# single-gates-THT.net
KiCad netlist of a schematic drawn in EAGLE
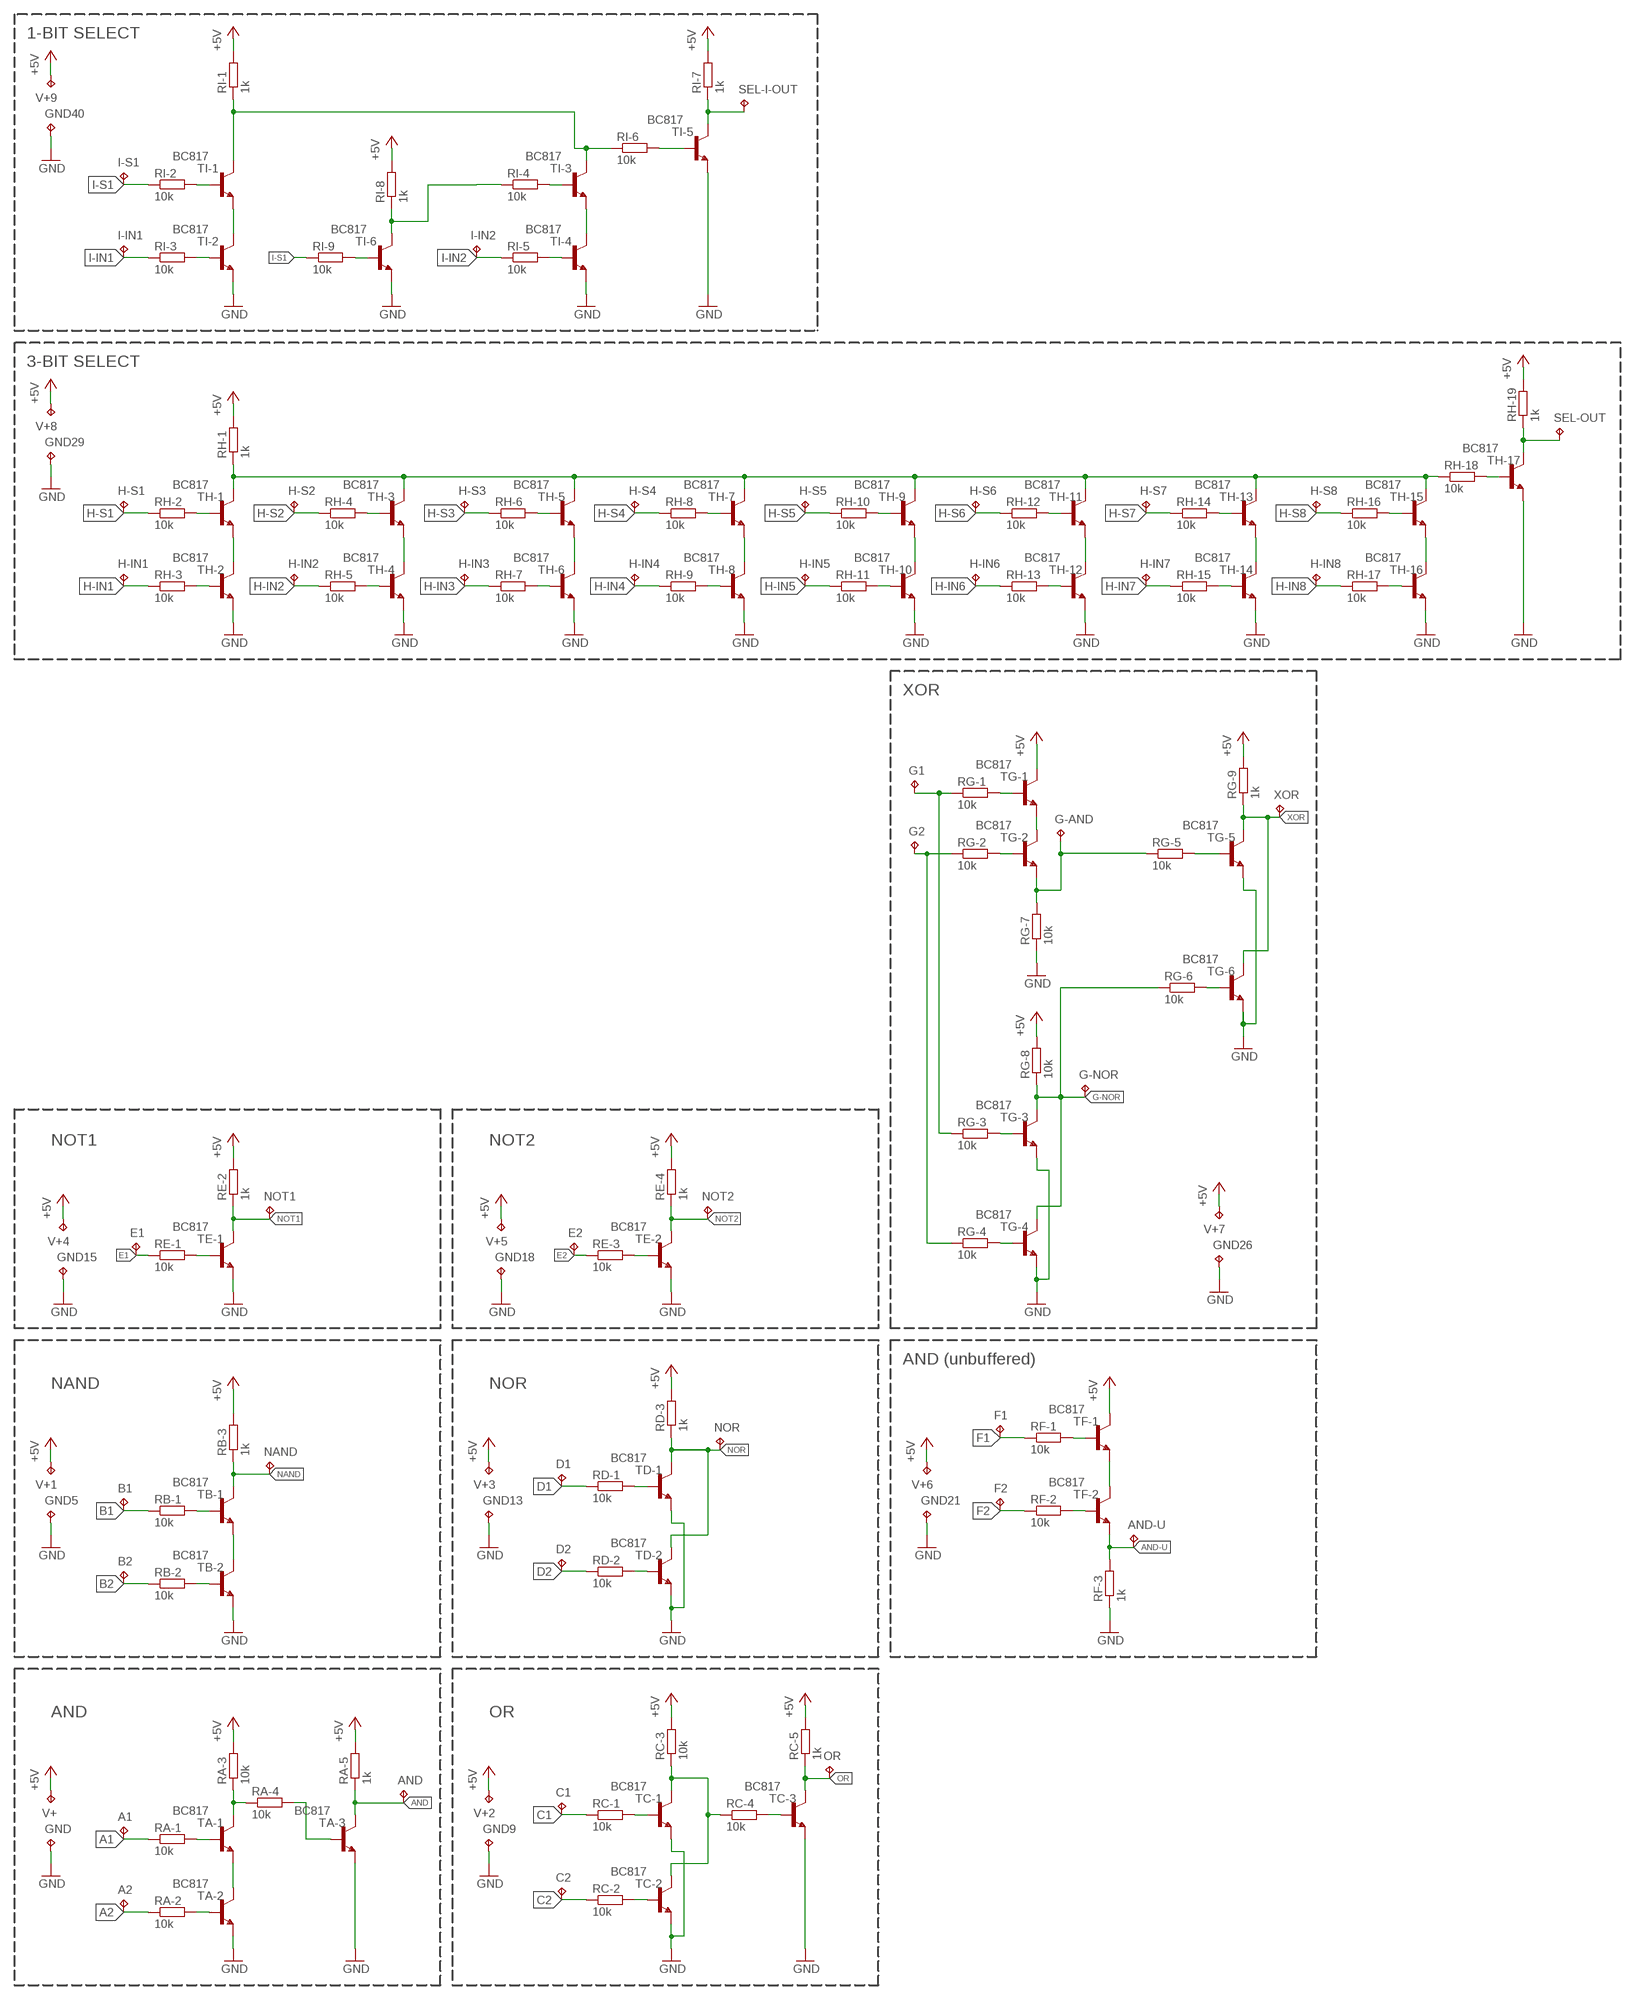
[diagram p0: schematic, sheet 1]

(export (version "E")
  (design (tool "Eeschema 10.0.6"))
  (components
    (comp (ref "A1")
      (value "TPTP07R")
      (footprint "eagle-import:TP07R")
      (libsource (lib "eagle-import") (part "TPTP07R"))
    )
    (comp (ref "A2")
      (value "TPTP07R")
      (footprint "eagle-import:TP07R")
      (libsource (lib "eagle-import") (part "TPTP07R"))
    )
    (comp (ref "AND")
      (value "TPTP07R")
      (footprint "eagle-import:TP07R")
      (libsource (lib "eagle-import") (part "TPTP07R"))
    )
    (comp (ref "AND-U")
      (value "TPTP07R")
      (footprint "eagle-import:TP07R")
      (libsource (lib "eagle-import") (part "TPTP07R"))
    )
    (comp (ref "B1")
      (value "TPTP07R")
      (footprint "eagle-import:TP07R")
      (libsource (lib "eagle-import") (part "TPTP07R"))
    )
    (comp (ref "B2")
      (value "TPTP07R")
      (footprint "eagle-import:TP07R")
      (libsource (lib "eagle-import") (part "TPTP07R"))
    )
    (comp (ref "C1")
      (value "TPTP07R")
      (footprint "eagle-import:TP07R")
      (libsource (lib "eagle-import") (part "TPTP07R"))
    )
    (comp (ref "C2")
      (value "TPTP07R")
      (footprint "eagle-import:TP07R")
      (libsource (lib "eagle-import") (part "TPTP07R"))
    )
    (comp (ref "D1")
      (value "TPTP07R")
      (footprint "eagle-import:TP07R")
      (libsource (lib "eagle-import") (part "TPTP07R"))
    )
    (comp (ref "D2")
      (value "TPTP07R")
      (footprint "eagle-import:TP07R")
      (libsource (lib "eagle-import") (part "TPTP07R"))
    )
    (comp (ref "E1")
      (value "TPTP07R")
      (footprint "eagle-import:TP07R")
      (libsource (lib "eagle-import") (part "TPTP07R"))
    )
    (comp (ref "E2")
      (value "TPTP07R")
      (footprint "eagle-import:TP07R")
      (libsource (lib "eagle-import") (part "TPTP07R"))
    )
    (comp (ref "F1")
      (value "TPTP07R")
      (footprint "eagle-import:TP07R")
      (libsource (lib "eagle-import") (part "TPTP07R"))
    )
    (comp (ref "F2")
      (value "TPTP07R")
      (footprint "eagle-import:TP07R")
      (libsource (lib "eagle-import") (part "TPTP07R"))
    )
    (comp (ref "G-AND")
      (value "TPTP07R")
      (footprint "eagle-import:TP07R")
      (libsource (lib "eagle-import") (part "TPTP07R"))
    )
    (comp (ref "G-NOR")
      (value "TPTP07R")
      (footprint "eagle-import:TP07R")
      (libsource (lib "eagle-import") (part "TPTP07R"))
    )
    (comp (ref "G1")
      (value "TPTP07R")
      (footprint "eagle-import:TP07R")
      (libsource (lib "eagle-import") (part "TPTP07R"))
    )
    (comp (ref "G2")
      (value "TPTP07R")
      (footprint "eagle-import:TP07R")
      (libsource (lib "eagle-import") (part "TPTP07R"))
    )
    (comp (ref "GND")
      (value "TPTP07R")
      (footprint "eagle-import:TP07R")
      (libsource (lib "eagle-import") (part "TPTP07R"))
    )
    (comp (ref "GND5")
      (value "TPTP07R")
      (footprint "eagle-import:TP07R")
      (libsource (lib "eagle-import") (part "TPTP07R"))
    )
    (comp (ref "GND9")
      (value "TPTP07R")
      (footprint "eagle-import:TP07R")
      (libsource (lib "eagle-import") (part "TPTP07R"))
    )
    (comp (ref "GND13")
      (value "TPTP07R")
      (footprint "eagle-import:TP07R")
      (libsource (lib "eagle-import") (part "TPTP07R"))
    )
    (comp (ref "GND15")
      (value "TPTP07R")
      (footprint "eagle-import:TP07R")
      (libsource (lib "eagle-import") (part "TPTP07R"))
    )
    (comp (ref "GND18")
      (value "TPTP07R")
      (footprint "eagle-import:TP07R")
      (libsource (lib "eagle-import") (part "TPTP07R"))
    )
    (comp (ref "GND21")
      (value "TPTP07R")
      (footprint "eagle-import:TP07R")
      (libsource (lib "eagle-import") (part "TPTP07R"))
    )
    (comp (ref "GND26")
      (value "TPTP07R")
      (footprint "eagle-import:TP07R")
      (libsource (lib "eagle-import") (part "TPTP07R"))
    )
    (comp (ref "GND29")
      (value "TPTP07R")
      (footprint "eagle-import:TP07R")
      (libsource (lib "eagle-import") (part "TPTP07R"))
    )
    (comp (ref "GND40")
      (value "TPTP07R")
      (footprint "eagle-import:TP07R")
      (libsource (lib "eagle-import") (part "TPTP07R"))
    )
    (comp (ref "H-IN1")
      (value "TPTP07R")
      (footprint "eagle-import:TP07R")
      (libsource (lib "eagle-import") (part "TPTP07R"))
    )
    (comp (ref "H-IN2")
      (value "TPTP07R")
      (footprint "eagle-import:TP07R")
      (libsource (lib "eagle-import") (part "TPTP07R"))
    )
    (comp (ref "H-IN3")
      (value "TPTP07R")
      (footprint "eagle-import:TP07R")
      (libsource (lib "eagle-import") (part "TPTP07R"))
    )
    (comp (ref "H-IN4")
      (value "TPTP07R")
      (footprint "eagle-import:TP07R")
      (libsource (lib "eagle-import") (part "TPTP07R"))
    )
    (comp (ref "H-IN5")
      (value "TPTP07R")
      (footprint "eagle-import:TP07R")
      (libsource (lib "eagle-import") (part "TPTP07R"))
    )
    (comp (ref "H-IN6")
      (value "TPTP07R")
      (footprint "eagle-import:TP07R")
      (libsource (lib "eagle-import") (part "TPTP07R"))
    )
    (comp (ref "H-IN7")
      (value "TPTP07R")
      (footprint "eagle-import:TP07R")
      (libsource (lib "eagle-import") (part "TPTP07R"))
    )
    (comp (ref "H-IN8")
      (value "TPTP07R")
      (footprint "eagle-import:TP07R")
      (libsource (lib "eagle-import") (part "TPTP07R"))
    )
    (comp (ref "H-S1")
      (value "TPTP07R")
      (footprint "eagle-import:TP07R")
      (libsource (lib "eagle-import") (part "TPTP07R"))
    )
    (comp (ref "H-S2")
      (value "TPTP07R")
      (footprint "eagle-import:TP07R")
      (libsource (lib "eagle-import") (part "TPTP07R"))
    )
    (comp (ref "H-S3")
      (value "TPTP07R")
      (footprint "eagle-import:TP07R")
      (libsource (lib "eagle-import") (part "TPTP07R"))
    )
    (comp (ref "H-S4")
      (value "TPTP07R")
      (footprint "eagle-import:TP07R")
      (libsource (lib "eagle-import") (part "TPTP07R"))
    )
    (comp (ref "H-S5")
      (value "TPTP07R")
      (footprint "eagle-import:TP07R")
      (libsource (lib "eagle-import") (part "TPTP07R"))
    )
    (comp (ref "H-S6")
      (value "TPTP07R")
      (footprint "eagle-import:TP07R")
      (libsource (lib "eagle-import") (part "TPTP07R"))
    )
    (comp (ref "H-S7")
      (value "TPTP07R")
      (footprint "eagle-import:TP07R")
      (libsource (lib "eagle-import") (part "TPTP07R"))
    )
    (comp (ref "H-S8")
      (value "TPTP07R")
      (footprint "eagle-import:TP07R")
      (libsource (lib "eagle-import") (part "TPTP07R"))
    )
    (comp (ref "I-IN1")
      (value "TPTP07R")
      (footprint "eagle-import:TP07R")
      (libsource (lib "eagle-import") (part "TPTP07R"))
    )
    (comp (ref "I-IN2")
      (value "TPTP07R")
      (footprint "eagle-import:TP07R")
      (libsource (lib "eagle-import") (part "TPTP07R"))
    )
    (comp (ref "I-S1")
      (value "TPTP07R")
      (footprint "eagle-import:TP07R")
      (libsource (lib "eagle-import") (part "TPTP07R"))
    )
    (comp (ref "NAND")
      (value "TPTP07R")
      (footprint "eagle-import:TP07R")
      (libsource (lib "eagle-import") (part "TPTP07R"))
    )
    (comp (ref "NOR")
      (value "TPTP07R")
      (footprint "eagle-import:TP07R")
      (libsource (lib "eagle-import") (part "TPTP07R"))
    )
    (comp (ref "NOT1")
      (value "TPTP07R")
      (footprint "eagle-import:TP07R")
      (libsource (lib "eagle-import") (part "TPTP07R"))
    )
    (comp (ref "NOT2")
      (value "TPTP07R")
      (footprint "eagle-import:TP07R")
      (libsource (lib "eagle-import") (part "TPTP07R"))
    )
    (comp (ref "OR")
      (value "TPTP07R")
      (footprint "eagle-import:TP07R")
      (libsource (lib "eagle-import") (part "TPTP07R"))
    )
    (comp (ref "RA-1")
      (value "10k")
      (footprint "eagle-import:0207_7")
      (libsource (lib "eagle-import") (part "R-EU_0207/7"))
    )
    (comp (ref "RA-2")
      (value "10k")
      (footprint "eagle-import:0207_7")
      (libsource (lib "eagle-import") (part "R-EU_0207/7"))
    )
    (comp (ref "RA-3")
      (value "10k")
      (footprint "eagle-import:0207_7")
      (libsource (lib "eagle-import") (part "R-EU_0207/7"))
    )
    (comp (ref "RA-4")
      (value "10k")
      (footprint "eagle-import:0207_7")
      (libsource (lib "eagle-import") (part "R-EU_0207/7"))
    )
    (comp (ref "RA-5")
      (value "1k")
      (footprint "eagle-import:0207_7")
      (libsource (lib "eagle-import") (part "R-EU_0207/7"))
    )
    (comp (ref "RB-1")
      (value "10k")
      (footprint "eagle-import:0207_7")
      (libsource (lib "eagle-import") (part "R-EU_0207/7"))
    )
    (comp (ref "RB-2")
      (value "10k")
      (footprint "eagle-import:0207_7")
      (libsource (lib "eagle-import") (part "R-EU_0207/7"))
    )
    (comp (ref "RB-3")
      (value "1k")
      (footprint "eagle-import:0207_7")
      (libsource (lib "eagle-import") (part "R-EU_0207/7"))
    )
    (comp (ref "RC-1")
      (value "10k")
      (footprint "eagle-import:0207_7")
      (libsource (lib "eagle-import") (part "R-EU_0207/7"))
    )
    (comp (ref "RC-2")
      (value "10k")
      (footprint "eagle-import:0207_7")
      (libsource (lib "eagle-import") (part "R-EU_0207/7"))
    )
    (comp (ref "RC-3")
      (value "10k")
      (footprint "eagle-import:0207_7")
      (libsource (lib "eagle-import") (part "R-EU_0207/7"))
    )
    (comp (ref "RC-4")
      (value "10k")
      (footprint "eagle-import:0207_7")
      (libsource (lib "eagle-import") (part "R-EU_0207/7"))
    )
    (comp (ref "RC-5")
      (value "1k")
      (footprint "eagle-import:0207_7")
      (libsource (lib "eagle-import") (part "R-EU_0207/7"))
    )
    (comp (ref "RD-1")
      (value "10k")
      (footprint "eagle-import:0207_7")
      (libsource (lib "eagle-import") (part "R-EU_0207/7"))
    )
    (comp (ref "RD-2")
      (value "10k")
      (footprint "eagle-import:0207_7")
      (libsource (lib "eagle-import") (part "R-EU_0207/7"))
    )
    (comp (ref "RD-3")
      (value "1k")
      (footprint "eagle-import:0207_7")
      (libsource (lib "eagle-import") (part "R-EU_0207/7"))
    )
    (comp (ref "RE-1")
      (value "10k")
      (footprint "eagle-import:0207_7")
      (libsource (lib "eagle-import") (part "R-EU_0207/7"))
    )
    (comp (ref "RE-2")
      (value "1k")
      (footprint "eagle-import:0207_7")
      (libsource (lib "eagle-import") (part "R-EU_0207/7"))
    )
    (comp (ref "RE-3")
      (value "10k")
      (footprint "eagle-import:0207_7")
      (libsource (lib "eagle-import") (part "R-EU_0207/7"))
    )
    (comp (ref "RE-4")
      (value "1k")
      (footprint "eagle-import:0207_7")
      (libsource (lib "eagle-import") (part "R-EU_0207/7"))
    )
    (comp (ref "RF-1")
      (value "10k")
      (footprint "eagle-import:0207_7")
      (libsource (lib "eagle-import") (part "R-EU_0207/7"))
    )
    (comp (ref "RF-2")
      (value "10k")
      (footprint "eagle-import:0207_7")
      (libsource (lib "eagle-import") (part "R-EU_0207/7"))
    )
    (comp (ref "RF-3")
      (value "1k")
      (footprint "eagle-import:0207_7")
      (libsource (lib "eagle-import") (part "R-EU_0207/7"))
    )
    (comp (ref "RG-1")
      (value "10k")
      (footprint "eagle-import:0207_7")
      (libsource (lib "eagle-import") (part "R-EU_0207/7"))
    )
    (comp (ref "RG-2")
      (value "10k")
      (footprint "eagle-import:0207_7")
      (libsource (lib "eagle-import") (part "R-EU_0207/7"))
    )
    (comp (ref "RG-3")
      (value "10k")
      (footprint "eagle-import:0207_7")
      (libsource (lib "eagle-import") (part "R-EU_0207/7"))
    )
    (comp (ref "RG-4")
      (value "10k")
      (footprint "eagle-import:0207_7")
      (libsource (lib "eagle-import") (part "R-EU_0207/7"))
    )
    (comp (ref "RG-5")
      (value "10k")
      (footprint "eagle-import:0207_7")
      (libsource (lib "eagle-import") (part "R-EU_0207/7"))
    )
    (comp (ref "RG-6")
      (value "10k")
      (footprint "eagle-import:0207_7")
      (libsource (lib "eagle-import") (part "R-EU_0207/7"))
    )
    (comp (ref "RG-7")
      (value "10k")
      (footprint "eagle-import:0207_7")
      (libsource (lib "eagle-import") (part "R-EU_0207/7"))
    )
    (comp (ref "RG-8")
      (value "10k")
      (footprint "eagle-import:0207_7")
      (libsource (lib "eagle-import") (part "R-EU_0207/7"))
    )
    (comp (ref "RG-9")
      (value "1k")
      (footprint "eagle-import:0207_7")
      (libsource (lib "eagle-import") (part "R-EU_0207/7"))
    )
    (comp (ref "RH-1")
      (value "1k")
      (footprint "eagle-import:0207_7")
      (libsource (lib "eagle-import") (part "R-EU_0207/7"))
    )
    (comp (ref "RH-2")
      (value "10k")
      (footprint "eagle-import:0207_7")
      (libsource (lib "eagle-import") (part "R-EU_0207/7"))
    )
    (comp (ref "RH-3")
      (value "10k")
      (footprint "eagle-import:0207_7")
      (libsource (lib "eagle-import") (part "R-EU_0207/7"))
    )
    (comp (ref "RH-4")
      (value "10k")
      (footprint "eagle-import:0207_7")
      (libsource (lib "eagle-import") (part "R-EU_0207/7"))
    )
    (comp (ref "RH-5")
      (value "10k")
      (footprint "eagle-import:0207_7")
      (libsource (lib "eagle-import") (part "R-EU_0207/7"))
    )
    (comp (ref "RH-6")
      (value "10k")
      (footprint "eagle-import:0207_7")
      (libsource (lib "eagle-import") (part "R-EU_0207/7"))
    )
    (comp (ref "RH-7")
      (value "10k")
      (footprint "eagle-import:0207_7")
      (libsource (lib "eagle-import") (part "R-EU_0207/7"))
    )
    (comp (ref "RH-8")
      (value "10k")
      (footprint "eagle-import:0207_7")
      (libsource (lib "eagle-import") (part "R-EU_0207/7"))
    )
    (comp (ref "RH-9")
      (value "10k")
      (footprint "eagle-import:0207_7")
      (libsource (lib "eagle-import") (part "R-EU_0207/7"))
    )
    (comp (ref "RH-10")
      (value "10k")
      (footprint "eagle-import:0207_7")
      (libsource (lib "eagle-import") (part "R-EU_0207/7"))
    )
    (comp (ref "RH-11")
      (value "10k")
      (footprint "eagle-import:0207_7")
      (libsource (lib "eagle-import") (part "R-EU_0207/7"))
    )
    (comp (ref "RH-12")
      (value "10k")
      (footprint "eagle-import:0207_7")
      (libsource (lib "eagle-import") (part "R-EU_0207/7"))
    )
    (comp (ref "RH-13")
      (value "10k")
      (footprint "eagle-import:0207_7")
      (libsource (lib "eagle-import") (part "R-EU_0207/7"))
    )
    (comp (ref "RH-14")
      (value "10k")
      (footprint "eagle-import:0207_7")
      (libsource (lib "eagle-import") (part "R-EU_0207/7"))
    )
    (comp (ref "RH-15")
      (value "10k")
      (footprint "eagle-import:0207_7")
      (libsource (lib "eagle-import") (part "R-EU_0207/7"))
    )
    (comp (ref "RH-16")
      (value "10k")
      (footprint "eagle-import:0207_7")
      (libsource (lib "eagle-import") (part "R-EU_0207/7"))
    )
    (comp (ref "RH-17")
      (value "10k")
      (footprint "eagle-import:0207_7")
      (libsource (lib "eagle-import") (part "R-EU_0207/7"))
    )
    (comp (ref "RH-18")
      (value "10k")
      (footprint "eagle-import:0207_7")
      (libsource (lib "eagle-import") (part "R-EU_0207/7"))
    )
    (comp (ref "RH-19")
      (value "1k")
      (footprint "eagle-import:0207_7")
      (libsource (lib "eagle-import") (part "R-EU_0207/7"))
    )
    (comp (ref "RI-1")
      (value "1k")
      (footprint "eagle-import:0207_7")
      (libsource (lib "eagle-import") (part "R-EU_0207/7"))
    )
    (comp (ref "RI-2")
      (value "10k")
      (footprint "eagle-import:0207_7")
      (libsource (lib "eagle-import") (part "R-EU_0207/7"))
    )
    (comp (ref "RI-3")
      (value "10k")
      (footprint "eagle-import:0207_7")
      (libsource (lib "eagle-import") (part "R-EU_0207/7"))
    )
    (comp (ref "RI-4")
      (value "10k")
      (footprint "eagle-import:0207_7")
      (libsource (lib "eagle-import") (part "R-EU_0207/7"))
    )
    (comp (ref "RI-5")
      (value "10k")
      (footprint "eagle-import:0207_7")
      (libsource (lib "eagle-import") (part "R-EU_0207/7"))
    )
    (comp (ref "RI-6")
      (value "10k")
      (footprint "eagle-import:0207_7")
      (libsource (lib "eagle-import") (part "R-EU_0207/7"))
    )
    (comp (ref "RI-7")
      (value "1k")
      (footprint "eagle-import:0207_7")
      (libsource (lib "eagle-import") (part "R-EU_0207/7"))
    )
    (comp (ref "RI-8")
      (value "1k")
      (footprint "eagle-import:0207_7")
      (libsource (lib "eagle-import") (part "R-EU_0207/7"))
    )
    (comp (ref "RI-9")
      (value "10k")
      (footprint "eagle-import:0207_7")
      (libsource (lib "eagle-import") (part "R-EU_0207/7"))
    )
    (comp (ref "SEL-I-OUT")
      (value "TPTP07R")
      (footprint "eagle-import:TP07R")
      (libsource (lib "eagle-import") (part "TPTP07R"))
    )
    (comp (ref "SEL-OUT")
      (value "TPTP07R")
      (footprint "eagle-import:TP07R")
      (libsource (lib "eagle-import") (part "TPTP07R"))
    )
    (comp (ref "TA-1")
      (value "BC817")
      (footprint "eagle-import:TO92")
      (libsource (lib "eagle-import") (part "BC547A"))
    )
    (comp (ref "TA-2")
      (value "BC817")
      (footprint "eagle-import:TO92")
      (libsource (lib "eagle-import") (part "BC547A"))
    )
    (comp (ref "TA-3")
      (value "BC817")
      (footprint "eagle-import:TO92")
      (libsource (lib "eagle-import") (part "BC547A"))
    )
    (comp (ref "TB-1")
      (value "BC817")
      (footprint "eagle-import:TO92")
      (libsource (lib "eagle-import") (part "BC547A"))
    )
    (comp (ref "TB-2")
      (value "BC817")
      (footprint "eagle-import:TO92")
      (libsource (lib "eagle-import") (part "BC547A"))
    )
    (comp (ref "TC-1")
      (value "BC817")
      (footprint "eagle-import:TO92")
      (libsource (lib "eagle-import") (part "BC547A"))
    )
    (comp (ref "TC-2")
      (value "BC817")
      (footprint "eagle-import:TO92")
      (libsource (lib "eagle-import") (part "BC547A"))
    )
    (comp (ref "TC-3")
      (value "BC817")
      (footprint "eagle-import:TO92")
      (libsource (lib "eagle-import") (part "BC547A"))
    )
    (comp (ref "TD-1")
      (value "BC817")
      (footprint "eagle-import:TO92")
      (libsource (lib "eagle-import") (part "BC547A"))
    )
    (comp (ref "TD-2")
      (value "BC817")
      (footprint "eagle-import:TO92")
      (libsource (lib "eagle-import") (part "BC547A"))
    )
    (comp (ref "TE-1")
      (value "BC817")
      (footprint "eagle-import:TO92")
      (libsource (lib "eagle-import") (part "BC547A"))
    )
    (comp (ref "TE-2")
      (value "BC817")
      (footprint "eagle-import:TO92")
      (libsource (lib "eagle-import") (part "BC547A"))
    )
    (comp (ref "TF-1")
      (value "BC817")
      (footprint "eagle-import:TO92")
      (libsource (lib "eagle-import") (part "BC547A"))
    )
    (comp (ref "TF-2")
      (value "BC817")
      (footprint "eagle-import:TO92")
      (libsource (lib "eagle-import") (part "BC547A"))
    )
    (comp (ref "TG-1")
      (value "BC817")
      (footprint "eagle-import:TO92")
      (libsource (lib "eagle-import") (part "BC547A"))
    )
    (comp (ref "TG-2")
      (value "BC817")
      (footprint "eagle-import:TO92")
      (libsource (lib "eagle-import") (part "BC547A"))
    )
    (comp (ref "TG-3")
      (value "BC817")
      (footprint "eagle-import:TO92")
      (libsource (lib "eagle-import") (part "BC547A"))
    )
    (comp (ref "TG-4")
      (value "BC817")
      (footprint "eagle-import:TO92")
      (libsource (lib "eagle-import") (part "BC547A"))
    )
    (comp (ref "TG-5")
      (value "BC817")
      (footprint "eagle-import:TO92")
      (libsource (lib "eagle-import") (part "BC547A"))
    )
    (comp (ref "TG-6")
      (value "BC817")
      (footprint "eagle-import:TO92")
      (libsource (lib "eagle-import") (part "BC547A"))
    )
    (comp (ref "TH-1")
      (value "BC817")
      (footprint "eagle-import:TO92")
      (libsource (lib "eagle-import") (part "BC547A"))
    )
    (comp (ref "TH-2")
      (value "BC817")
      (footprint "eagle-import:TO92")
      (libsource (lib "eagle-import") (part "BC547A"))
    )
    (comp (ref "TH-3")
      (value "BC817")
      (footprint "eagle-import:TO92")
      (libsource (lib "eagle-import") (part "BC547A"))
    )
    (comp (ref "TH-4")
      (value "BC817")
      (footprint "eagle-import:TO92")
      (libsource (lib "eagle-import") (part "BC547A"))
    )
    (comp (ref "TH-5")
      (value "BC817")
      (footprint "eagle-import:TO92")
      (libsource (lib "eagle-import") (part "BC547A"))
    )
    (comp (ref "TH-6")
      (value "BC817")
      (footprint "eagle-import:TO92")
      (libsource (lib "eagle-import") (part "BC547A"))
    )
    (comp (ref "TH-7")
      (value "BC817")
      (footprint "eagle-import:TO92")
      (libsource (lib "eagle-import") (part "BC547A"))
    )
    (comp (ref "TH-8")
      (value "BC817")
      (footprint "eagle-import:TO92")
      (libsource (lib "eagle-import") (part "BC547A"))
    )
    (comp (ref "TH-9")
      (value "BC817")
      (footprint "eagle-import:TO92")
      (libsource (lib "eagle-import") (part "BC547A"))
    )
    (comp (ref "TH-10")
      (value "BC817")
      (footprint "eagle-import:TO92")
      (libsource (lib "eagle-import") (part "BC547A"))
    )
    (comp (ref "TH-11")
      (value "BC817")
      (footprint "eagle-import:TO92")
      (libsource (lib "eagle-import") (part "BC547A"))
    )
    (comp (ref "TH-12")
      (value "BC817")
      (footprint "eagle-import:TO92")
      (libsource (lib "eagle-import") (part "BC547A"))
    )
    (comp (ref "TH-13")
      (value "BC817")
      (footprint "eagle-import:TO92")
      (libsource (lib "eagle-import") (part "BC547A"))
    )
    (comp (ref "TH-14")
      (value "BC817")
      (footprint "eagle-import:TO92")
      (libsource (lib "eagle-import") (part "BC547A"))
    )
    (comp (ref "TH-15")
      (value "BC817")
      (footprint "eagle-import:TO92")
      (libsource (lib "eagle-import") (part "BC547A"))
    )
    (comp (ref "TH-16")
      (value "BC817")
      (footprint "eagle-import:TO92")
      (libsource (lib "eagle-import") (part "BC547A"))
    )
    (comp (ref "TH-17")
      (value "BC817")
      (footprint "eagle-import:TO92")
      (libsource (lib "eagle-import") (part "BC547A"))
    )
    (comp (ref "TI-1")
      (value "BC817")
      (footprint "eagle-import:TO92")
      (libsource (lib "eagle-import") (part "BC547A"))
    )
    (comp (ref "TI-2")
      (value "BC817")
      (footprint "eagle-import:TO92")
      (libsource (lib "eagle-import") (part "BC547A"))
    )
    (comp (ref "TI-3")
      (value "BC817")
      (footprint "eagle-import:TO92")
      (libsource (lib "eagle-import") (part "BC547A"))
    )
    (comp (ref "TI-4")
      (value "BC817")
      (footprint "eagle-import:TO92")
      (libsource (lib "eagle-import") (part "BC547A"))
    )
    (comp (ref "TI-5")
      (value "BC817")
      (footprint "eagle-import:TO92")
      (libsource (lib "eagle-import") (part "BC547A"))
    )
    (comp (ref "TI-6")
      (value "BC817")
      (footprint "eagle-import:TO92")
      (libsource (lib "eagle-import") (part "BC547A"))
    )
    (comp (ref "V+")
      (value "TPTP07R")
      (footprint "eagle-import:TP07R")
      (libsource (lib "eagle-import") (part "TPTP07R"))
    )
    (comp (ref "V+1")
      (value "TPTP07R")
      (footprint "eagle-import:TP07R")
      (libsource (lib "eagle-import") (part "TPTP07R"))
    )
    (comp (ref "V+2")
      (value "TPTP07R")
      (footprint "eagle-import:TP07R")
      (libsource (lib "eagle-import") (part "TPTP07R"))
    )
    (comp (ref "V+3")
      (value "TPTP07R")
      (footprint "eagle-import:TP07R")
      (libsource (lib "eagle-import") (part "TPTP07R"))
    )
    (comp (ref "V+4")
      (value "TPTP07R")
      (footprint "eagle-import:TP07R")
      (libsource (lib "eagle-import") (part "TPTP07R"))
    )
    (comp (ref "V+5")
      (value "TPTP07R")
      (footprint "eagle-import:TP07R")
      (libsource (lib "eagle-import") (part "TPTP07R"))
    )
    (comp (ref "V+6")
      (value "TPTP07R")
      (footprint "eagle-import:TP07R")
      (libsource (lib "eagle-import") (part "TPTP07R"))
    )
    (comp (ref "V+7")
      (value "TPTP07R")
      (footprint "eagle-import:TP07R")
      (libsource (lib "eagle-import") (part "TPTP07R"))
    )
    (comp (ref "V+8")
      (value "TPTP07R")
      (footprint "eagle-import:TP07R")
      (libsource (lib "eagle-import") (part "TPTP07R"))
    )
    (comp (ref "V+9")
      (value "TPTP07R")
      (footprint "eagle-import:TP07R")
      (libsource (lib "eagle-import") (part "TPTP07R"))
    )
    (comp (ref "XOR")
      (value "TPTP07R")
      (footprint "eagle-import:TP07R")
      (libsource (lib "eagle-import") (part "TPTP07R"))
    )
  )
  (nets
    (net (code "1") (name "+5V") (class "Default")
      (node (ref "RA-3") (pin "2") (pinfunction "2_2") (pintype "passive"))
      (node (ref "RA-5") (pin "2") (pinfunction "2_2") (pintype "passive"))
      (node (ref "RB-3") (pin "2") (pinfunction "2_2") (pintype "passive"))
      (node (ref "RC-3") (pin "2") (pinfunction "2_2") (pintype "passive"))
      (node (ref "RC-5") (pin "2") (pinfunction "2_2") (pintype "passive"))
      (node (ref "RD-3") (pin "2") (pinfunction "2_2") (pintype "passive"))
      (node (ref "RE-2") (pin "2") (pinfunction "2_2") (pintype "passive"))
      (node (ref "RE-4") (pin "2") (pinfunction "2_2") (pintype "passive"))
      (node (ref "RG-8") (pin "2") (pinfunction "2_2") (pintype "passive"))
      (node (ref "RG-9") (pin "2") (pinfunction "2_2") (pintype "passive"))
      (node (ref "RH-1") (pin "2") (pinfunction "2_2") (pintype "passive"))
      (node (ref "RH-19") (pin "2") (pinfunction "2_2") (pintype "passive"))
      (node (ref "RI-1") (pin "2") (pinfunction "2_2") (pintype "passive"))
      (node (ref "RI-7") (pin "2") (pinfunction "2_2") (pintype "passive"))
      (node (ref "RI-8") (pin "2") (pinfunction "2_2") (pintype "passive"))
      (node (ref "TF-1") (pin "3") (pinfunction "C_3") (pintype "passive"))
      (node (ref "TG-1") (pin "3") (pinfunction "C_3") (pintype "passive"))
      (node (ref "V+") (pin "TP") (pinfunction "TP_TP") (pintype "input"))
      (node (ref "V+1") (pin "TP") (pinfunction "TP_TP") (pintype "input"))
      (node (ref "V+2") (pin "TP") (pinfunction "TP_TP") (pintype "input"))
      (node (ref "V+3") (pin "TP") (pinfunction "TP_TP") (pintype "input"))
      (node (ref "V+4") (pin "TP") (pinfunction "TP_TP") (pintype "input"))
      (node (ref "V+5") (pin "TP") (pinfunction "TP_TP") (pintype "input"))
      (node (ref "V+6") (pin "TP") (pinfunction "TP_TP") (pintype "input"))
      (node (ref "V+7") (pin "TP") (pinfunction "TP_TP") (pintype "input"))
      (node (ref "V+8") (pin "TP") (pinfunction "TP_TP") (pintype "input"))
      (node (ref "V+9") (pin "TP") (pinfunction "TP_TP") (pintype "input"))
    )
    (net (code "2") (name "A1") (class "Default")
      (node (ref "A1") (pin "TP") (pinfunction "TP_TP") (pintype "input"))
      (node (ref "RA-1") (pin "1") (pinfunction "1_1") (pintype "passive"))
    )
    (net (code "3") (name "A2") (class "Default")
      (node (ref "A2") (pin "TP") (pinfunction "TP_TP") (pintype "input"))
      (node (ref "RA-2") (pin "1") (pinfunction "1_1") (pintype "passive"))
    )
    (net (code "4") (name "AND") (class "Default")
      (node (ref "AND") (pin "TP") (pinfunction "TP_TP") (pintype "input"))
      (node (ref "RA-5") (pin "1") (pinfunction "1_1") (pintype "passive"))
      (node (ref "TA-3") (pin "3") (pinfunction "C_3") (pintype "passive"))
    )
    (net (code "5") (name "AND-U") (class "Default")
      (node (ref "AND-U") (pin "TP") (pinfunction "TP_TP") (pintype "input"))
      (node (ref "RF-3") (pin "2") (pinfunction "2_2") (pintype "passive"))
      (node (ref "TF-2") (pin "1") (pinfunction "E_1") (pintype "passive"))
    )
    (net (code "6") (name "B1") (class "Default")
      (node (ref "B1") (pin "TP") (pinfunction "TP_TP") (pintype "input"))
      (node (ref "RB-1") (pin "1") (pinfunction "1_1") (pintype "passive"))
    )
    (net (code "7") (name "B2") (class "Default")
      (node (ref "B2") (pin "TP") (pinfunction "TP_TP") (pintype "input"))
      (node (ref "RB-2") (pin "1") (pinfunction "1_1") (pintype "passive"))
    )
    (net (code "8") (name "C1") (class "Default")
      (node (ref "C1") (pin "TP") (pinfunction "TP_TP") (pintype "input"))
      (node (ref "RC-1") (pin "1") (pinfunction "1_1") (pintype "passive"))
    )
    (net (code "9") (name "C2") (class "Default")
      (node (ref "C2") (pin "TP") (pinfunction "TP_TP") (pintype "input"))
      (node (ref "RC-2") (pin "1") (pinfunction "1_1") (pintype "passive"))
    )
    (net (code "10") (name "D1") (class "Default")
      (node (ref "D1") (pin "TP") (pinfunction "TP_TP") (pintype "input"))
      (node (ref "RD-1") (pin "1") (pinfunction "1_1") (pintype "passive"))
    )
    (net (code "11") (name "D2") (class "Default")
      (node (ref "D2") (pin "TP") (pinfunction "TP_TP") (pintype "input"))
      (node (ref "RD-2") (pin "1") (pinfunction "1_1") (pintype "passive"))
    )
    (net (code "12") (name "E1") (class "Default")
      (node (ref "E1") (pin "TP") (pinfunction "TP_TP") (pintype "input"))
      (node (ref "RE-1") (pin "1") (pinfunction "1_1") (pintype "passive"))
    )
    (net (code "13") (name "E2") (class "Default")
      (node (ref "E2") (pin "TP") (pinfunction "TP_TP") (pintype "input"))
      (node (ref "RE-3") (pin "1") (pinfunction "1_1") (pintype "passive"))
    )
    (net (code "14") (name "F1") (class "Default")
      (node (ref "F1") (pin "TP") (pinfunction "TP_TP") (pintype "input"))
      (node (ref "RF-1") (pin "1") (pinfunction "1_1") (pintype "passive"))
    )
    (net (code "15") (name "F2") (class "Default")
      (node (ref "F2") (pin "TP") (pinfunction "TP_TP") (pintype "input"))
      (node (ref "RF-2") (pin "1") (pinfunction "1_1") (pintype "passive"))
    )
    (net (code "16") (name "G-NOR") (class "Default")
      (node (ref "G-NOR") (pin "TP") (pinfunction "TP_TP") (pintype "input"))
      (node (ref "RG-6") (pin "1") (pinfunction "1_1") (pintype "passive"))
      (node (ref "RG-8") (pin "1") (pinfunction "1_1") (pintype "passive"))
      (node (ref "TG-3") (pin "3") (pinfunction "C_3") (pintype "passive"))
      (node (ref "TG-4") (pin "3") (pinfunction "C_3") (pintype "passive"))
    )
    (net (code "17") (name "GND") (class "Default")
      (node (ref "GND") (pin "TP") (pinfunction "TP_TP") (pintype "input"))
      (node (ref "GND13") (pin "TP") (pinfunction "TP_TP") (pintype "input"))
      (node (ref "GND15") (pin "TP") (pinfunction "TP_TP") (pintype "input"))
      (node (ref "GND18") (pin "TP") (pinfunction "TP_TP") (pintype "input"))
      (node (ref "GND21") (pin "TP") (pinfunction "TP_TP") (pintype "input"))
      (node (ref "GND26") (pin "TP") (pinfunction "TP_TP") (pintype "input"))
      (node (ref "GND29") (pin "TP") (pinfunction "TP_TP") (pintype "input"))
      (node (ref "GND40") (pin "TP") (pinfunction "TP_TP") (pintype "input"))
      (node (ref "GND5") (pin "TP") (pinfunction "TP_TP") (pintype "input"))
      (node (ref "GND9") (pin "TP") (pinfunction "TP_TP") (pintype "input"))
      (node (ref "RF-3") (pin "1") (pinfunction "1_1") (pintype "passive"))
      (node (ref "RG-7") (pin "1") (pinfunction "1_1") (pintype "passive"))
      (node (ref "TA-2") (pin "1") (pinfunction "E_1") (pintype "passive"))
      (node (ref "TA-3") (pin "1") (pinfunction "E_1") (pintype "passive"))
      (node (ref "TB-2") (pin "1") (pinfunction "E_1") (pintype "passive"))
      (node (ref "TC-1") (pin "1") (pinfunction "E_1") (pintype "passive"))
      (node (ref "TC-2") (pin "1") (pinfunction "E_1") (pintype "passive"))
      (node (ref "TC-3") (pin "1") (pinfunction "E_1") (pintype "passive"))
      (node (ref "TD-1") (pin "1") (pinfunction "E_1") (pintype "passive"))
      (node (ref "TD-2") (pin "1") (pinfunction "E_1") (pintype "passive"))
      (node (ref "TE-1") (pin "1") (pinfunction "E_1") (pintype "passive"))
      (node (ref "TE-2") (pin "1") (pinfunction "E_1") (pintype "passive"))
      (node (ref "TG-3") (pin "1") (pinfunction "E_1") (pintype "passive"))
      (node (ref "TG-4") (pin "1") (pinfunction "E_1") (pintype "passive"))
      (node (ref "TG-5") (pin "1") (pinfunction "E_1") (pintype "passive"))
      (node (ref "TG-6") (pin "1") (pinfunction "E_1") (pintype "passive"))
      (node (ref "TH-10") (pin "1") (pinfunction "E_1") (pintype "passive"))
      (node (ref "TH-12") (pin "1") (pinfunction "E_1") (pintype "passive"))
      (node (ref "TH-14") (pin "1") (pinfunction "E_1") (pintype "passive"))
      (node (ref "TH-16") (pin "1") (pinfunction "E_1") (pintype "passive"))
      (node (ref "TH-17") (pin "1") (pinfunction "E_1") (pintype "passive"))
      (node (ref "TH-2") (pin "1") (pinfunction "E_1") (pintype "passive"))
      (node (ref "TH-4") (pin "1") (pinfunction "E_1") (pintype "passive"))
      (node (ref "TH-6") (pin "1") (pinfunction "E_1") (pintype "passive"))
      (node (ref "TH-8") (pin "1") (pinfunction "E_1") (pintype "passive"))
      (node (ref "TI-2") (pin "1") (pinfunction "E_1") (pintype "passive"))
      (node (ref "TI-4") (pin "1") (pinfunction "E_1") (pintype "passive"))
      (node (ref "TI-5") (pin "1") (pinfunction "E_1") (pintype "passive"))
      (node (ref "TI-6") (pin "1") (pinfunction "E_1") (pintype "passive"))
    )
    (net (code "18") (name "H-IN1") (class "Default")
      (node (ref "H-IN1") (pin "TP") (pinfunction "TP_TP") (pintype "input"))
      (node (ref "RH-3") (pin "1") (pinfunction "1_1") (pintype "passive"))
    )
    (net (code "19") (name "H-IN2") (class "Default")
      (node (ref "H-IN2") (pin "TP") (pinfunction "TP_TP") (pintype "input"))
      (node (ref "RH-5") (pin "1") (pinfunction "1_1") (pintype "passive"))
    )
    (net (code "20") (name "H-IN3") (class "Default")
      (node (ref "H-IN3") (pin "TP") (pinfunction "TP_TP") (pintype "input"))
      (node (ref "RH-7") (pin "1") (pinfunction "1_1") (pintype "passive"))
    )
    (net (code "21") (name "H-IN4") (class "Default")
      (node (ref "H-IN4") (pin "TP") (pinfunction "TP_TP") (pintype "input"))
      (node (ref "RH-9") (pin "1") (pinfunction "1_1") (pintype "passive"))
    )
    (net (code "22") (name "H-IN5") (class "Default")
      (node (ref "H-IN5") (pin "TP") (pinfunction "TP_TP") (pintype "input"))
      (node (ref "RH-11") (pin "1") (pinfunction "1_1") (pintype "passive"))
    )
    (net (code "23") (name "H-IN6") (class "Default")
      (node (ref "H-IN6") (pin "TP") (pinfunction "TP_TP") (pintype "input"))
      (node (ref "RH-13") (pin "1") (pinfunction "1_1") (pintype "passive"))
    )
    (net (code "24") (name "H-IN7") (class "Default")
      (node (ref "H-IN7") (pin "TP") (pinfunction "TP_TP") (pintype "input"))
      (node (ref "RH-15") (pin "1") (pinfunction "1_1") (pintype "passive"))
    )
    (net (code "25") (name "H-IN8") (class "Default")
      (node (ref "H-IN8") (pin "TP") (pinfunction "TP_TP") (pintype "input"))
      (node (ref "RH-17") (pin "1") (pinfunction "1_1") (pintype "passive"))
    )
    (net (code "26") (name "H-S1") (class "Default")
      (node (ref "H-S1") (pin "TP") (pinfunction "TP_TP") (pintype "input"))
      (node (ref "RH-2") (pin "1") (pinfunction "1_1") (pintype "passive"))
    )
    (net (code "27") (name "H-S2") (class "Default")
      (node (ref "H-S2") (pin "TP") (pinfunction "TP_TP") (pintype "input"))
      (node (ref "RH-4") (pin "1") (pinfunction "1_1") (pintype "passive"))
    )
    (net (code "28") (name "H-S3") (class "Default")
      (node (ref "H-S3") (pin "TP") (pinfunction "TP_TP") (pintype "input"))
      (node (ref "RH-6") (pin "1") (pinfunction "1_1") (pintype "passive"))
    )
    (net (code "29") (name "H-S4") (class "Default")
      (node (ref "H-S4") (pin "TP") (pinfunction "TP_TP") (pintype "input"))
      (node (ref "RH-8") (pin "1") (pinfunction "1_1") (pintype "passive"))
    )
    (net (code "30") (name "H-S5") (class "Default")
      (node (ref "H-S5") (pin "TP") (pinfunction "TP_TP") (pintype "input"))
      (node (ref "RH-10") (pin "1") (pinfunction "1_1") (pintype "passive"))
    )
    (net (code "31") (name "H-S6") (class "Default")
      (node (ref "H-S6") (pin "TP") (pinfunction "TP_TP") (pintype "input"))
      (node (ref "RH-12") (pin "1") (pinfunction "1_1") (pintype "passive"))
    )
    (net (code "32") (name "H-S7") (class "Default")
      (node (ref "H-S7") (pin "TP") (pinfunction "TP_TP") (pintype "input"))
      (node (ref "RH-14") (pin "1") (pinfunction "1_1") (pintype "passive"))
    )
    (net (code "33") (name "H-S8") (class "Default")
      (node (ref "H-S8") (pin "TP") (pinfunction "TP_TP") (pintype "input"))
      (node (ref "RH-16") (pin "1") (pinfunction "1_1") (pintype "passive"))
    )
    (net (code "34") (name "I-IN1") (class "Default")
      (node (ref "I-IN1") (pin "TP") (pinfunction "TP_TP") (pintype "input"))
      (node (ref "RI-3") (pin "1") (pinfunction "1_1") (pintype "passive"))
    )
    (net (code "35") (name "I-IN2") (class "Default")
      (node (ref "I-IN2") (pin "TP") (pinfunction "TP_TP") (pintype "input"))
      (node (ref "RI-5") (pin "1") (pinfunction "1_1") (pintype "passive"))
    )
    (net (code "36") (name "I-S1") (class "Default")
      (node (ref "I-S1") (pin "TP") (pinfunction "TP_TP") (pintype "input"))
      (node (ref "RI-2") (pin "1") (pinfunction "1_1") (pintype "passive"))
      (node (ref "RI-9") (pin "1") (pinfunction "1_1") (pintype "passive"))
    )
    (net (code "37") (name "NAND") (class "Default")
      (node (ref "NAND") (pin "TP") (pinfunction "TP_TP") (pintype "input"))
      (node (ref "RB-3") (pin "1") (pinfunction "1_1") (pintype "passive"))
      (node (ref "TB-1") (pin "3") (pinfunction "C_3") (pintype "passive"))
    )
    (net (code "38") (name "NOR") (class "Default")
      (node (ref "NOR") (pin "TP") (pinfunction "TP_TP") (pintype "input"))
      (node (ref "RD-3") (pin "1") (pinfunction "1_1") (pintype "passive"))
      (node (ref "TD-1") (pin "3") (pinfunction "C_3") (pintype "passive"))
      (node (ref "TD-2") (pin "3") (pinfunction "C_3") (pintype "passive"))
    )
    (net (code "39") (name "NOT1") (class "Default")
      (node (ref "NOT1") (pin "TP") (pinfunction "TP_TP") (pintype "input"))
      (node (ref "RE-2") (pin "1") (pinfunction "1_1") (pintype "passive"))
      (node (ref "TE-1") (pin "3") (pinfunction "C_3") (pintype "passive"))
    )
    (net (code "40") (name "NOT2") (class "Default")
      (node (ref "NOT2") (pin "TP") (pinfunction "TP_TP") (pintype "input"))
      (node (ref "RE-4") (pin "1") (pinfunction "1_1") (pintype "passive"))
      (node (ref "TE-2") (pin "3") (pinfunction "C_3") (pintype "passive"))
    )
    (net (code "41") (name "Net-(G1-PadTP)") (class "Default")
      (node (ref "G1") (pin "TP") (pinfunction "TP_TP") (pintype "input"))
      (node (ref "RG-1") (pin "1") (pinfunction "1_1") (pintype "passive"))
      (node (ref "RG-3") (pin "1") (pinfunction "1_1") (pintype "passive"))
    )
    (net (code "42") (name "Net-(G2-PadTP)") (class "Default")
      (node (ref "G2") (pin "TP") (pinfunction "TP_TP") (pintype "input"))
      (node (ref "RG-2") (pin "1") (pinfunction "1_1") (pintype "passive"))
      (node (ref "RG-4") (pin "1") (pinfunction "1_1") (pintype "passive"))
    )
    (net (code "43") (name "Net-(TA-1-B)") (class "Default")
      (node (ref "RA-1") (pin "2") (pinfunction "2_2") (pintype "passive"))
      (node (ref "TA-1") (pin "2") (pinfunction "B_2") (pintype "passive"))
    )
    (net (code "44") (name "Net-(TA-1-C)") (class "Default")
      (node (ref "RA-3") (pin "1") (pinfunction "1_1") (pintype "passive"))
      (node (ref "RA-4") (pin "1") (pinfunction "1_1") (pintype "passive"))
      (node (ref "TA-1") (pin "3") (pinfunction "C_3") (pintype "passive"))
    )
    (net (code "45") (name "Net-(TA-1-E)") (class "Default")
      (node (ref "TA-1") (pin "1") (pinfunction "E_1") (pintype "passive"))
      (node (ref "TA-2") (pin "3") (pinfunction "C_3") (pintype "passive"))
    )
    (net (code "46") (name "Net-(TA-2-B)") (class "Default")
      (node (ref "RA-2") (pin "2") (pinfunction "2_2") (pintype "passive"))
      (node (ref "TA-2") (pin "2") (pinfunction "B_2") (pintype "passive"))
    )
    (net (code "47") (name "Net-(TA-3-B)") (class "Default")
      (node (ref "RA-4") (pin "2") (pinfunction "2_2") (pintype "passive"))
      (node (ref "TA-3") (pin "2") (pinfunction "B_2") (pintype "passive"))
    )
    (net (code "48") (name "Net-(TB-1-B)") (class "Default")
      (node (ref "RB-1") (pin "2") (pinfunction "2_2") (pintype "passive"))
      (node (ref "TB-1") (pin "2") (pinfunction "B_2") (pintype "passive"))
    )
    (net (code "49") (name "Net-(TB-1-E)") (class "Default")
      (node (ref "TB-1") (pin "1") (pinfunction "E_1") (pintype "passive"))
      (node (ref "TB-2") (pin "3") (pinfunction "C_3") (pintype "passive"))
    )
    (net (code "50") (name "Net-(TB-2-B)") (class "Default")
      (node (ref "RB-2") (pin "2") (pinfunction "2_2") (pintype "passive"))
      (node (ref "TB-2") (pin "2") (pinfunction "B_2") (pintype "passive"))
    )
    (net (code "51") (name "Net-(TC-1-B)") (class "Default")
      (node (ref "RC-1") (pin "2") (pinfunction "2_2") (pintype "passive"))
      (node (ref "TC-1") (pin "2") (pinfunction "B_2") (pintype "passive"))
    )
    (net (code "52") (name "Net-(TC-1-C)") (class "Default")
      (node (ref "RC-3") (pin "1") (pinfunction "1_1") (pintype "passive"))
      (node (ref "RC-4") (pin "1") (pinfunction "1_1") (pintype "passive"))
      (node (ref "TC-1") (pin "3") (pinfunction "C_3") (pintype "passive"))
      (node (ref "TC-2") (pin "3") (pinfunction "C_3") (pintype "passive"))
    )
    (net (code "53") (name "Net-(TC-2-B)") (class "Default")
      (node (ref "RC-2") (pin "2") (pinfunction "2_2") (pintype "passive"))
      (node (ref "TC-2") (pin "2") (pinfunction "B_2") (pintype "passive"))
    )
    (net (code "54") (name "Net-(TC-3-B)") (class "Default")
      (node (ref "RC-4") (pin "2") (pinfunction "2_2") (pintype "passive"))
      (node (ref "TC-3") (pin "2") (pinfunction "B_2") (pintype "passive"))
    )
    (net (code "55") (name "Net-(TD-1-B)") (class "Default")
      (node (ref "RD-1") (pin "2") (pinfunction "2_2") (pintype "passive"))
      (node (ref "TD-1") (pin "2") (pinfunction "B_2") (pintype "passive"))
    )
    (net (code "56") (name "Net-(TD-2-B)") (class "Default")
      (node (ref "RD-2") (pin "2") (pinfunction "2_2") (pintype "passive"))
      (node (ref "TD-2") (pin "2") (pinfunction "B_2") (pintype "passive"))
    )
    (net (code "57") (name "Net-(TE-1-B)") (class "Default")
      (node (ref "RE-1") (pin "2") (pinfunction "2_2") (pintype "passive"))
      (node (ref "TE-1") (pin "2") (pinfunction "B_2") (pintype "passive"))
    )
    (net (code "58") (name "Net-(TE-2-B)") (class "Default")
      (node (ref "RE-3") (pin "2") (pinfunction "2_2") (pintype "passive"))
      (node (ref "TE-2") (pin "2") (pinfunction "B_2") (pintype "passive"))
    )
    (net (code "59") (name "Net-(TF-1-B)") (class "Default")
      (node (ref "RF-1") (pin "2") (pinfunction "2_2") (pintype "passive"))
      (node (ref "TF-1") (pin "2") (pinfunction "B_2") (pintype "passive"))
    )
    (net (code "60") (name "Net-(TF-1-E)") (class "Default")
      (node (ref "TF-1") (pin "1") (pinfunction "E_1") (pintype "passive"))
      (node (ref "TF-2") (pin "3") (pinfunction "C_3") (pintype "passive"))
    )
    (net (code "61") (name "Net-(TF-2-B)") (class "Default")
      (node (ref "RF-2") (pin "2") (pinfunction "2_2") (pintype "passive"))
      (node (ref "TF-2") (pin "2") (pinfunction "B_2") (pintype "passive"))
    )
    (net (code "62") (name "Net-(TG-1-B)") (class "Default")
      (node (ref "RG-1") (pin "2") (pinfunction "2_2") (pintype "passive"))
      (node (ref "TG-1") (pin "2") (pinfunction "B_2") (pintype "passive"))
    )
    (net (code "63") (name "Net-(TG-1-E)") (class "Default")
      (node (ref "TG-1") (pin "1") (pinfunction "E_1") (pintype "passive"))
      (node (ref "TG-2") (pin "3") (pinfunction "C_3") (pintype "passive"))
    )
    (net (code "64") (name "Net-(TG-2-B)") (class "Default")
      (node (ref "RG-2") (pin "2") (pinfunction "2_2") (pintype "passive"))
      (node (ref "TG-2") (pin "2") (pinfunction "B_2") (pintype "passive"))
    )
    (net (code "65") (name "Net-(TG-2-E)") (class "Default")
      (node (ref "G-AND") (pin "TP") (pinfunction "TP_TP") (pintype "input"))
      (node (ref "RG-5") (pin "1") (pinfunction "1_1") (pintype "passive"))
      (node (ref "RG-7") (pin "2") (pinfunction "2_2") (pintype "passive"))
      (node (ref "TG-2") (pin "1") (pinfunction "E_1") (pintype "passive"))
    )
    (net (code "66") (name "Net-(TG-3-B)") (class "Default")
      (node (ref "RG-3") (pin "2") (pinfunction "2_2") (pintype "passive"))
      (node (ref "TG-3") (pin "2") (pinfunction "B_2") (pintype "passive"))
    )
    (net (code "67") (name "Net-(TG-4-B)") (class "Default")
      (node (ref "RG-4") (pin "2") (pinfunction "2_2") (pintype "passive"))
      (node (ref "TG-4") (pin "2") (pinfunction "B_2") (pintype "passive"))
    )
    (net (code "68") (name "Net-(TG-5-B)") (class "Default")
      (node (ref "RG-5") (pin "2") (pinfunction "2_2") (pintype "passive"))
      (node (ref "TG-5") (pin "2") (pinfunction "B_2") (pintype "passive"))
    )
    (net (code "69") (name "Net-(TG-6-B)") (class "Default")
      (node (ref "RG-6") (pin "2") (pinfunction "2_2") (pintype "passive"))
      (node (ref "TG-6") (pin "2") (pinfunction "B_2") (pintype "passive"))
    )
    (net (code "70") (name "Net-(TH-1-B)") (class "Default")
      (node (ref "RH-2") (pin "2") (pinfunction "2_2") (pintype "passive"))
      (node (ref "TH-1") (pin "2") (pinfunction "B_2") (pintype "passive"))
    )
    (net (code "71") (name "Net-(TH-1-C)") (class "Default")
      (node (ref "RH-1") (pin "1") (pinfunction "1_1") (pintype "passive"))
      (node (ref "RH-18") (pin "1") (pinfunction "1_1") (pintype "passive"))
      (node (ref "TH-1") (pin "3") (pinfunction "C_3") (pintype "passive"))
      (node (ref "TH-11") (pin "3") (pinfunction "C_3") (pintype "passive"))
      (node (ref "TH-13") (pin "3") (pinfunction "C_3") (pintype "passive"))
      (node (ref "TH-15") (pin "3") (pinfunction "C_3") (pintype "passive"))
      (node (ref "TH-3") (pin "3") (pinfunction "C_3") (pintype "passive"))
      (node (ref "TH-5") (pin "3") (pinfunction "C_3") (pintype "passive"))
      (node (ref "TH-7") (pin "3") (pinfunction "C_3") (pintype "passive"))
      (node (ref "TH-9") (pin "3") (pinfunction "C_3") (pintype "passive"))
    )
    (net (code "72") (name "Net-(TH-1-E)") (class "Default")
      (node (ref "TH-1") (pin "1") (pinfunction "E_1") (pintype "passive"))
      (node (ref "TH-2") (pin "3") (pinfunction "C_3") (pintype "passive"))
    )
    (net (code "73") (name "Net-(TH-2-B)") (class "Default")
      (node (ref "RH-3") (pin "2") (pinfunction "2_2") (pintype "passive"))
      (node (ref "TH-2") (pin "2") (pinfunction "B_2") (pintype "passive"))
    )
    (net (code "74") (name "Net-(TH-3-B)") (class "Default")
      (node (ref "RH-4") (pin "2") (pinfunction "2_2") (pintype "passive"))
      (node (ref "TH-3") (pin "2") (pinfunction "B_2") (pintype "passive"))
    )
    (net (code "75") (name "Net-(TH-3-E)") (class "Default")
      (node (ref "TH-3") (pin "1") (pinfunction "E_1") (pintype "passive"))
      (node (ref "TH-4") (pin "3") (pinfunction "C_3") (pintype "passive"))
    )
    (net (code "76") (name "Net-(TH-4-B)") (class "Default")
      (node (ref "RH-5") (pin "2") (pinfunction "2_2") (pintype "passive"))
      (node (ref "TH-4") (pin "2") (pinfunction "B_2") (pintype "passive"))
    )
    (net (code "77") (name "Net-(TH-5-B)") (class "Default")
      (node (ref "RH-6") (pin "2") (pinfunction "2_2") (pintype "passive"))
      (node (ref "TH-5") (pin "2") (pinfunction "B_2") (pintype "passive"))
    )
    (net (code "78") (name "Net-(TH-5-E)") (class "Default")
      (node (ref "TH-5") (pin "1") (pinfunction "E_1") (pintype "passive"))
      (node (ref "TH-6") (pin "3") (pinfunction "C_3") (pintype "passive"))
    )
    (net (code "79") (name "Net-(TH-6-B)") (class "Default")
      (node (ref "RH-7") (pin "2") (pinfunction "2_2") (pintype "passive"))
      (node (ref "TH-6") (pin "2") (pinfunction "B_2") (pintype "passive"))
    )
    (net (code "80") (name "Net-(TH-7-B)") (class "Default")
      (node (ref "RH-8") (pin "2") (pinfunction "2_2") (pintype "passive"))
      (node (ref "TH-7") (pin "2") (pinfunction "B_2") (pintype "passive"))
    )
    (net (code "81") (name "Net-(TH-7-E)") (class "Default")
      (node (ref "TH-7") (pin "1") (pinfunction "E_1") (pintype "passive"))
      (node (ref "TH-8") (pin "3") (pinfunction "C_3") (pintype "passive"))
    )
    (net (code "82") (name "Net-(TH-8-B)") (class "Default")
      (node (ref "RH-9") (pin "2") (pinfunction "2_2") (pintype "passive"))
      (node (ref "TH-8") (pin "2") (pinfunction "B_2") (pintype "passive"))
    )
    (net (code "83") (name "Net-(TH-9-B)") (class "Default")
      (node (ref "RH-10") (pin "2") (pinfunction "2_2") (pintype "passive"))
      (node (ref "TH-9") (pin "2") (pinfunction "B_2") (pintype "passive"))
    )
    (net (code "84") (name "Net-(TH-10-B)") (class "Default")
      (node (ref "RH-11") (pin "2") (pinfunction "2_2") (pintype "passive"))
      (node (ref "TH-10") (pin "2") (pinfunction "B_2") (pintype "passive"))
    )
    (net (code "85") (name "Net-(TH-10-C)") (class "Default")
      (node (ref "TH-10") (pin "3") (pinfunction "C_3") (pintype "passive"))
      (node (ref "TH-9") (pin "1") (pinfunction "E_1") (pintype "passive"))
    )
    (net (code "86") (name "Net-(TH-11-B)") (class "Default")
      (node (ref "RH-12") (pin "2") (pinfunction "2_2") (pintype "passive"))
      (node (ref "TH-11") (pin "2") (pinfunction "B_2") (pintype "passive"))
    )
    (net (code "87") (name "Net-(TH-11-E)") (class "Default")
      (node (ref "TH-11") (pin "1") (pinfunction "E_1") (pintype "passive"))
      (node (ref "TH-12") (pin "3") (pinfunction "C_3") (pintype "passive"))
    )
    (net (code "88") (name "Net-(TH-12-B)") (class "Default")
      (node (ref "RH-13") (pin "2") (pinfunction "2_2") (pintype "passive"))
      (node (ref "TH-12") (pin "2") (pinfunction "B_2") (pintype "passive"))
    )
    (net (code "89") (name "Net-(TH-13-B)") (class "Default")
      (node (ref "RH-14") (pin "2") (pinfunction "2_2") (pintype "passive"))
      (node (ref "TH-13") (pin "2") (pinfunction "B_2") (pintype "passive"))
    )
    (net (code "90") (name "Net-(TH-13-E)") (class "Default")
      (node (ref "TH-13") (pin "1") (pinfunction "E_1") (pintype "passive"))
      (node (ref "TH-14") (pin "3") (pinfunction "C_3") (pintype "passive"))
    )
    (net (code "91") (name "Net-(TH-14-B)") (class "Default")
      (node (ref "RH-15") (pin "2") (pinfunction "2_2") (pintype "passive"))
      (node (ref "TH-14") (pin "2") (pinfunction "B_2") (pintype "passive"))
    )
    (net (code "92") (name "Net-(TH-15-B)") (class "Default")
      (node (ref "RH-16") (pin "2") (pinfunction "2_2") (pintype "passive"))
      (node (ref "TH-15") (pin "2") (pinfunction "B_2") (pintype "passive"))
    )
    (net (code "93") (name "Net-(TH-15-E)") (class "Default")
      (node (ref "TH-15") (pin "1") (pinfunction "E_1") (pintype "passive"))
      (node (ref "TH-16") (pin "3") (pinfunction "C_3") (pintype "passive"))
    )
    (net (code "94") (name "Net-(TH-16-B)") (class "Default")
      (node (ref "RH-17") (pin "2") (pinfunction "2_2") (pintype "passive"))
      (node (ref "TH-16") (pin "2") (pinfunction "B_2") (pintype "passive"))
    )
    (net (code "95") (name "Net-(TH-17-B)") (class "Default")
      (node (ref "RH-18") (pin "2") (pinfunction "2_2") (pintype "passive"))
      (node (ref "TH-17") (pin "2") (pinfunction "B_2") (pintype "passive"))
    )
    (net (code "96") (name "Net-(TH-17-C)") (class "Default")
      (node (ref "RH-19") (pin "1") (pinfunction "1_1") (pintype "passive"))
      (node (ref "SEL-OUT") (pin "TP") (pinfunction "TP_TP") (pintype "input"))
      (node (ref "TH-17") (pin "3") (pinfunction "C_3") (pintype "passive"))
    )
    (net (code "97") (name "Net-(TI-1-B)") (class "Default")
      (node (ref "RI-2") (pin "2") (pinfunction "2_2") (pintype "passive"))
      (node (ref "TI-1") (pin "2") (pinfunction "B_2") (pintype "passive"))
    )
    (net (code "98") (name "Net-(TI-1-C)") (class "Default")
      (node (ref "RI-1") (pin "1") (pinfunction "1_1") (pintype "passive"))
      (node (ref "RI-6") (pin "1") (pinfunction "1_1") (pintype "passive"))
      (node (ref "TI-1") (pin "3") (pinfunction "C_3") (pintype "passive"))
      (node (ref "TI-3") (pin "3") (pinfunction "C_3") (pintype "passive"))
    )
    (net (code "99") (name "Net-(TI-1-E)") (class "Default")
      (node (ref "TI-1") (pin "1") (pinfunction "E_1") (pintype "passive"))
      (node (ref "TI-2") (pin "3") (pinfunction "C_3") (pintype "passive"))
    )
    (net (code "100") (name "Net-(TI-2-B)") (class "Default")
      (node (ref "RI-3") (pin "2") (pinfunction "2_2") (pintype "passive"))
      (node (ref "TI-2") (pin "2") (pinfunction "B_2") (pintype "passive"))
    )
    (net (code "101") (name "Net-(TI-3-B)") (class "Default")
      (node (ref "RI-4") (pin "2") (pinfunction "2_2") (pintype "passive"))
      (node (ref "TI-3") (pin "2") (pinfunction "B_2") (pintype "passive"))
    )
    (net (code "102") (name "Net-(TI-3-E)") (class "Default")
      (node (ref "TI-3") (pin "1") (pinfunction "E_1") (pintype "passive"))
      (node (ref "TI-4") (pin "3") (pinfunction "C_3") (pintype "passive"))
    )
    (net (code "103") (name "Net-(TI-4-B)") (class "Default")
      (node (ref "RI-5") (pin "2") (pinfunction "2_2") (pintype "passive"))
      (node (ref "TI-4") (pin "2") (pinfunction "B_2") (pintype "passive"))
    )
    (net (code "104") (name "Net-(TI-5-B)") (class "Default")
      (node (ref "RI-6") (pin "2") (pinfunction "2_2") (pintype "passive"))
      (node (ref "TI-5") (pin "2") (pinfunction "B_2") (pintype "passive"))
    )
    (net (code "105") (name "Net-(TI-5-C)") (class "Default")
      (node (ref "RI-7") (pin "1") (pinfunction "1_1") (pintype "passive"))
      (node (ref "SEL-I-OUT") (pin "TP") (pinfunction "TP_TP") (pintype "input"))
      (node (ref "TI-5") (pin "3") (pinfunction "C_3") (pintype "passive"))
    )
    (net (code "106") (name "Net-(TI-6-B)") (class "Default")
      (node (ref "RI-9") (pin "2") (pinfunction "2_2") (pintype "passive"))
      (node (ref "TI-6") (pin "2") (pinfunction "B_2") (pintype "passive"))
    )
    (net (code "107") (name "Net-(TI-6-C)") (class "Default")
      (node (ref "RI-4") (pin "1") (pinfunction "1_1") (pintype "passive"))
      (node (ref "RI-8") (pin "1") (pinfunction "1_1") (pintype "passive"))
      (node (ref "TI-6") (pin "3") (pinfunction "C_3") (pintype "passive"))
    )
    (net (code "108") (name "OR") (class "Default")
      (node (ref "OR") (pin "TP") (pinfunction "TP_TP") (pintype "input"))
      (node (ref "RC-5") (pin "1") (pinfunction "1_1") (pintype "passive"))
      (node (ref "TC-3") (pin "3") (pinfunction "C_3") (pintype "passive"))
    )
    (net (code "109") (name "XOR") (class "Default")
      (node (ref "RG-9") (pin "1") (pinfunction "1_1") (pintype "passive"))
      (node (ref "TG-5") (pin "3") (pinfunction "C_3") (pintype "passive"))
      (node (ref "TG-6") (pin "3") (pinfunction "C_3") (pintype "passive"))
      (node (ref "XOR") (pin "TP") (pinfunction "TP_TP") (pintype "input"))
    )
  )
)
